# 01-PWR.net
KiCad netlist of a schematic drawn in Altium Designer
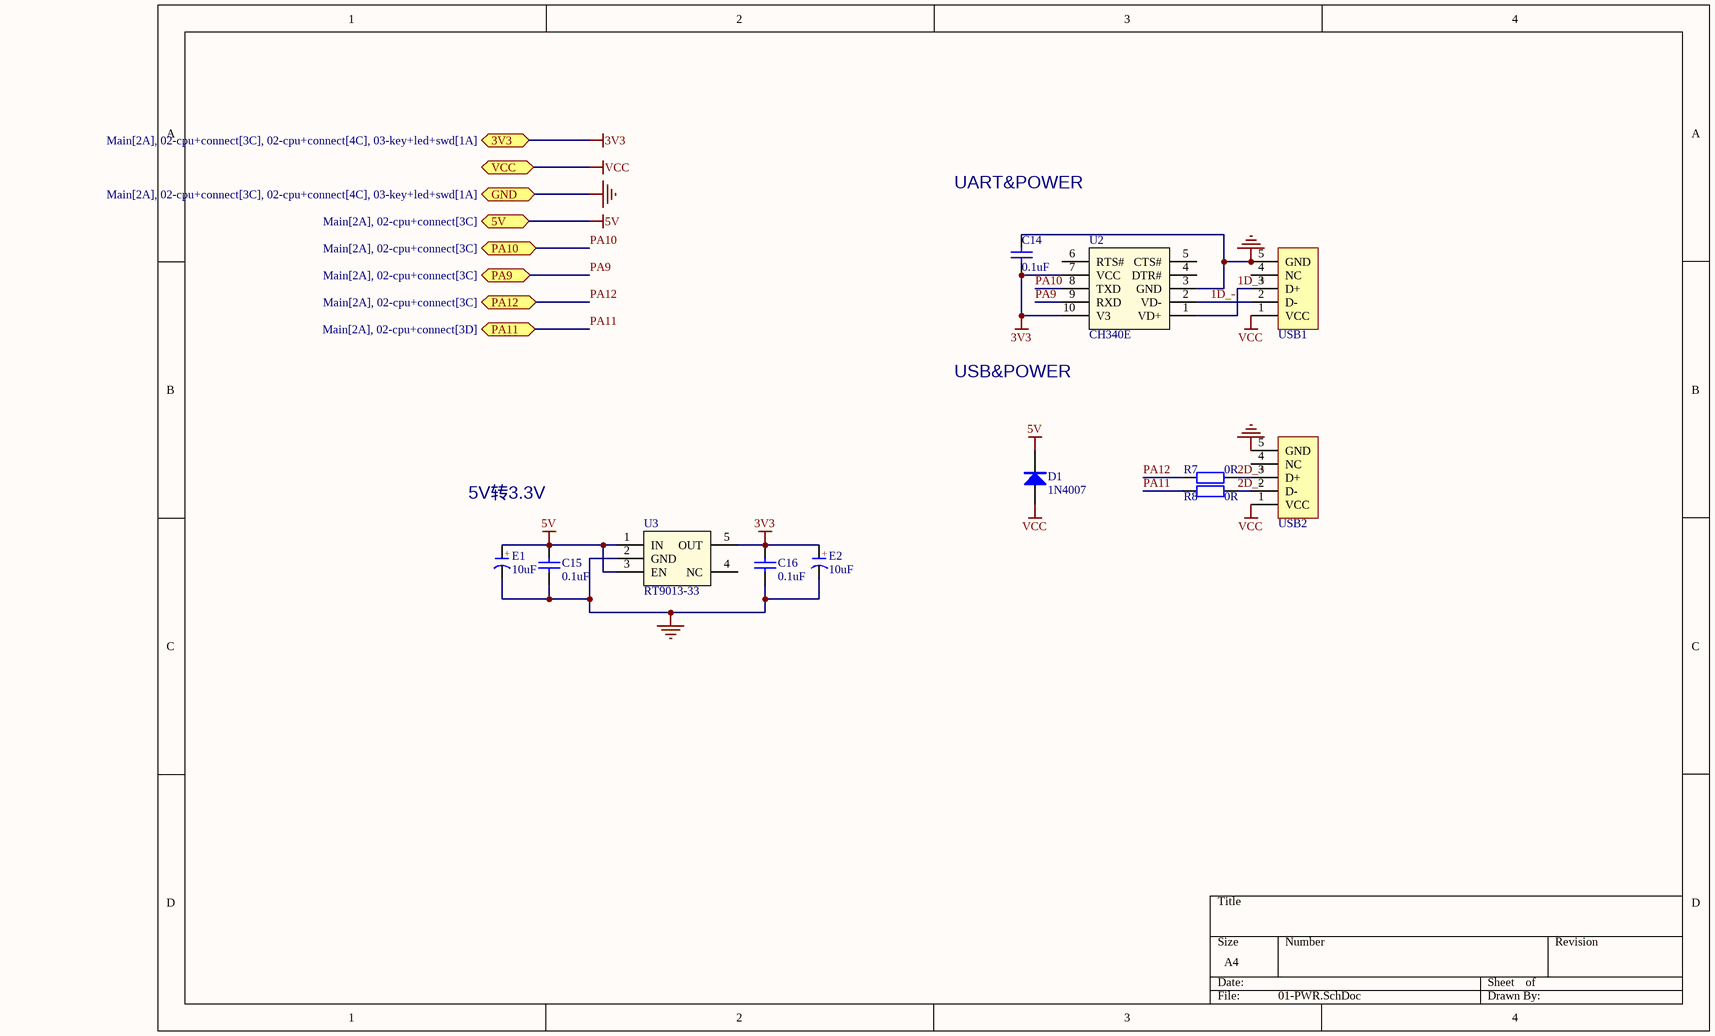
[diagram p0: 01-PWR.SchDoc]

(export (version "E")
  (design (tool "Eeschema 10.0.6"))
  (components
    (comp (ref "C14") (value "0.1uF") (footprint "C 0402_L") (libsource (lib "Schlib1") (part "Cap")))
    (comp (ref "C15") (value "0.1uF") (footprint "C 0402_L") (libsource (lib "Schlib1") (part "Cap")))
    (comp (ref "C16") (value "0.1uF") (footprint "C 0402_L") (libsource (lib "Schlib1") (part "Cap")))
    (comp (ref "D1")
      (value "1N4007")
      (footprint "SOD-123")
      (description "整流二极管")
      (libsource (lib "Schlib1") (part "1N4007"))
    )
    (comp (ref "E1")
      (value "10uF")
      (footprint "CD A(3216)")
      (description "贴片钽电容")
      (libsource (lib "Schlib1") (part "C-CD"))
    )
    (comp (ref "E2")
      (value "10uF")
      (footprint "CD A(3216)")
      (description "贴片钽电容")
      (libsource (lib "Schlib1") (part "C-CD"))
    )
    (comp (ref "R7") (value "0R") (footprint "R 0402_L") (libsource (lib "Schlib1") (part "Res")))
    (comp (ref "R8") (value "0R") (footprint "R 0402_L") (libsource (lib "Schlib1") (part "Res")))
    (comp (ref "U2") (value "CH340E") (footprint "MSOP10_L") (libsource (lib "Schlib1") (part "CH340E")))
    (comp (ref "U3")
      (value "RT9013-33")
      (footprint "SOT23-5N")
      (libsource (lib "Schlib1") (part "RT9013-33"))
    )
    (comp (ref "USB1") (value "USB") (footprint "USB-MICRO_E") (libsource (lib "Schlib1") (part "USB")))
    (comp (ref "USB2") (value "USB") (footprint "USB-MICRO_E") (libsource (lib "Schlib1") (part "USB")))
  )
  (nets
    (net (code "1") (name "/1D_+") (class "Default")
      (node (ref "U2") (pin "1") (pinfunction "VD+_1") (pintype "passive"))
      (node (ref "USB1") (pin "3") (pinfunction "D+_3") (pintype "passive"))
    )
    (net (code "2") (name "/1D_-") (class "Default")
      (node (ref "U2") (pin "2") (pinfunction "VD-_2") (pintype "passive"))
      (node (ref "USB1") (pin "2") (pinfunction "D-_2") (pintype "passive"))
    )
    (net (code "3") (name "/2D_+") (class "Default")
      (node (ref "R7") (pin "1") (pinfunction "1_1") (pintype "passive"))
      (node (ref "USB2") (pin "3") (pinfunction "D+_3") (pintype "passive"))
    )
    (net (code "4") (name "/2D_-") (class "Default")
      (node (ref "R8") (pin "1") (pinfunction "1_1") (pintype "passive"))
      (node (ref "USB2") (pin "2") (pinfunction "D-_2") (pintype "passive"))
    )
    (net (code "5") (name "/PA9") (class "Default")
      (node (ref "U2") (pin "9") (pinfunction "RXD_9") (pintype "passive"))
    )
    (net (code "6") (name "/PA10") (class "Default")
      (node (ref "U2") (pin "8") (pinfunction "TXD_8") (pintype "passive"))
    )
    (net (code "7") (name "/PA11") (class "Default")
      (node (ref "R8") (pin "2") (pinfunction "2_2") (pintype "passive"))
    )
    (net (code "8") (name "/PA12") (class "Default")
      (node (ref "R7") (pin "2") (pinfunction "2_2") (pintype "passive"))
    )
    (net (code "9") (name "3V3") (class "Default")
      (node (ref "C14") (pin "2") (pinfunction "2_2") (pintype "passive"))
      (node (ref "C16") (pin "2") (pinfunction "2_2") (pintype "passive"))
      (node (ref "E2") (pin "1") (pinfunction "A_1") (pintype "passive"))
      (node (ref "U2") (pin "10") (pinfunction "V3_10") (pintype "passive"))
      (node (ref "U2") (pin "7") (pinfunction "VCC_7") (pintype "passive"))
      (node (ref "U3") (pin "5") (pinfunction "OUT_5") (pintype "passive"))
    )
    (net (code "10") (name "5V") (class "Default")
      (node (ref "C15") (pin "2") (pinfunction "2_2") (pintype "passive"))
      (node (ref "D1") (pin "2") (pinfunction "K_2") (pintype "passive"))
      (node (ref "E1") (pin "1") (pinfunction "A_1") (pintype "passive"))
      (node (ref "U3") (pin "1") (pinfunction "IN_1") (pintype "passive"))
      (node (ref "U3") (pin "3") (pinfunction "EN_3") (pintype "passive"))
    )
    (net (code "11") (name "GND") (class "Default")
      (node (ref "C14") (pin "1") (pinfunction "1_1") (pintype "passive"))
      (node (ref "C15") (pin "1") (pinfunction "1_1") (pintype "passive"))
      (node (ref "C16") (pin "1") (pinfunction "1_1") (pintype "passive"))
      (node (ref "E1") (pin "2") (pinfunction "K_2") (pintype "passive"))
      (node (ref "E2") (pin "2") (pinfunction "K_2") (pintype "passive"))
      (node (ref "U2") (pin "3") (pinfunction "GND_3") (pintype "passive"))
      (node (ref "U3") (pin "2") (pinfunction "GND_2") (pintype "passive"))
      (node (ref "USB1") (pin "5") (pinfunction "GND_5") (pintype "passive"))
      (node (ref "USB2") (pin "5") (pinfunction "GND_5") (pintype "passive"))
    )
    (net (code "12") (name "VCC") (class "Default")
      (node (ref "D1") (pin "1") (pinfunction "A_1") (pintype "passive"))
      (node (ref "USB1") (pin "1") (pinfunction "VCC_1") (pintype "passive"))
      (node (ref "USB2") (pin "1") (pinfunction "VCC_1") (pintype "passive"))
    )
    (net (code "13") (name "unconnected-(U2-CTS#-Pad5)") (class "Default")
      (node (ref "U2") (pin "5") (pinfunction "CTS#_5") (pintype "passive"))
    )
    (net (code "14") (name "unconnected-(U2-DTR#-Pad4)") (class "Default")
      (node (ref "U2") (pin "4") (pinfunction "DTR#_4") (pintype "passive"))
    )
    (net (code "15") (name "unconnected-(U2-RTS#-Pad6)") (class "Default")
      (node (ref "U2") (pin "6") (pinfunction "RTS#_6") (pintype "passive"))
    )
    (net (code "16") (name "unconnected-(U3-NC-Pad4)") (class "Default")
      (node (ref "U3") (pin "4") (pinfunction "NC_4") (pintype "passive"))
    )
    (net (code "17") (name "unconnected-(USB1-NC-Pad4)") (class "Default")
      (node (ref "USB1") (pin "4") (pinfunction "NC_4") (pintype "passive"))
    )
    (net (code "18") (name "unconnected-(USB2-NC-Pad4)") (class "Default")
      (node (ref "USB2") (pin "4") (pinfunction "NC_4") (pintype "passive"))
    )
  )
)
